# Enable_Pulse_fire.net
KiCad netlist of a schematic drawn in Altium Designer
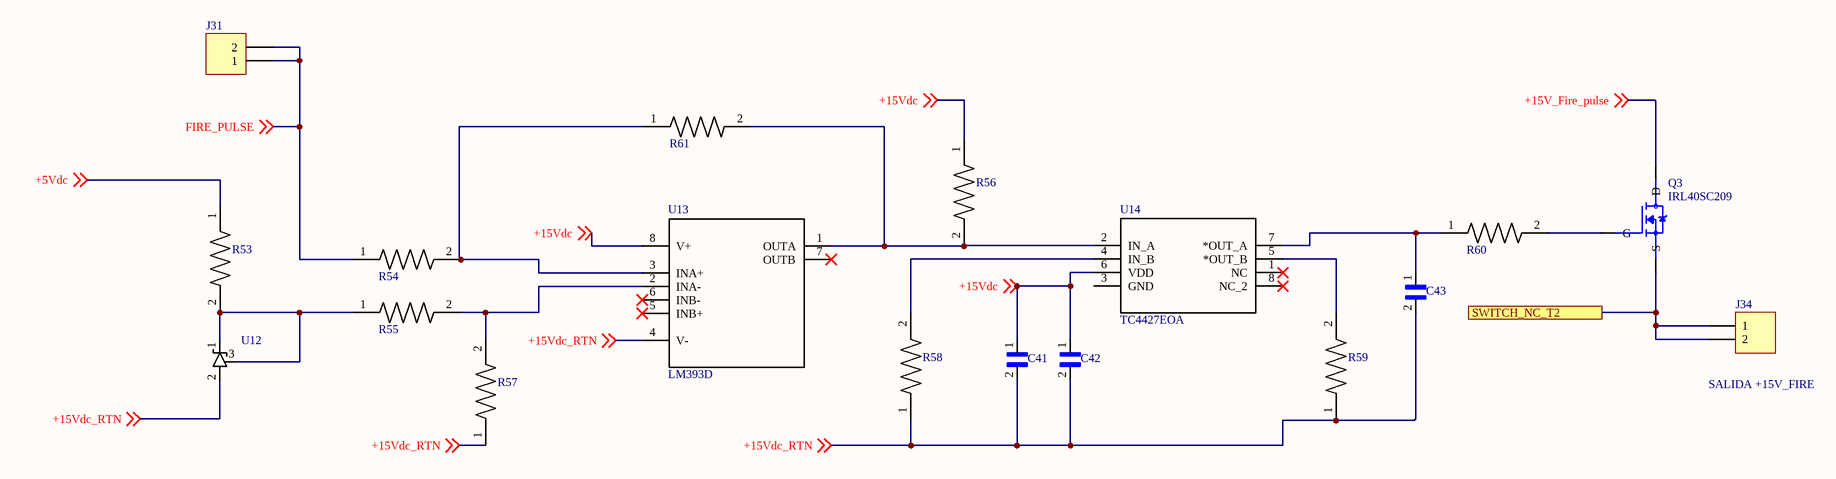
[diagram p0: Enable_Pulse_fire.SchDoc]

(export (version "E")
  (design (tool "Eeschema 10.0.6"))
  (components
    (comp (ref "C41")
      (value "UMK316AC7475KLHTE")
      (footprint "MLCC SMD 1206")
      (description "1216 50V 4.7uF 10% X7S")
      (libsource (lib "Schlib1") (part "Taiyo Yuden"))
    )
    (comp (ref "C42")
      (value "UMF316B7105KLHT")
      (footprint "MLCC SMD 1206")
      (description "1206 50V 1uF 10%")
      (libsource (lib "Schlib1") (part "Taiyo Yuden"))
    )
    (comp (ref "C43")
      (value "UMF316B7103MFHT")
      (footprint "MLCC SMD 1206")
      (description "1206 50V 0.01uF 20%")
      (libsource (lib "Schlib1") (part "Taiyo Yuden"))
    )
    (comp (ref "J31")
      (value "Header 2")
      (footprint "HDR1X2")
      (description "Header, 2-Pin")
      (fields (field (name "PUBLISHER") "Altium Limited"))
      (libsource (lib "Miscellaneous Connectors") (part "Header 2"))
    )
    (comp (ref "J34")
      (value "Header 2")
      (footprint "HDR1X2")
      (description "Header, 2-Pin")
      (fields (field (name "PUBLISHER") "Altium Limited"))
      (libsource (lib "") (part "Header 2_1"))
    )
    (comp (ref "Q3")
      (value "IRL40SC209")
      (footprint "D2PAK-7")
      (description "MOSFET TRENCH <= 40V")
      (libsource (lib "Schlib1") (part "IRL40SC209"))
    )
    (comp (ref "R53")
      (value "RCG12061K00FKEA")
      (footprint "Vishay Resistor 1206")
      (description "1K")
      (libsource (lib "Schlib1") (part "Vishay"))
    )
    (comp (ref "R54")
      (value "RCG12061K00FKEA")
      (footprint "Vishay Resistor 1206")
      (description "1K")
      (libsource (lib "") (part "Vishay_1"))
    )
    (comp (ref "R55")
      (value "RCG12061K00FKEA")
      (footprint "Vishay Resistor 1206")
      (description "1K")
      (libsource (lib "") (part "Vishay_1"))
    )
    (comp (ref "R56")
      (value "RCG12061K00FKEA")
      (footprint "Vishay Resistor 1206")
      (description "1K")
      (libsource (lib "") (part "Vishay_1"))
    )
    (comp (ref "R57")
      (value "CRCW12064K02FKEAC")
      (footprint "Vishay Resistor 1206")
      (description "4K")
      (libsource (lib "") (part "Vishay_1"))
    )
    (comp (ref "R58")
      (value "CRCW12060000Z0EAC")
      (footprint "Vishay Resistor 1206")
      (description "0OHM")
      (libsource (lib "") (part "Vishay_1"))
    )
    (comp (ref "R59")
      (value "CRCW12060000Z0EAC")
      (footprint "Vishay Resistor 1206")
      (description "0OHM")
      (libsource (lib "") (part "Vishay_1"))
    )
    (comp (ref "R60")
      (value "CRCW12064R70FKEAC")
      (footprint "Vishay Resistor 1206")
      (description "4.7OHM")
      (libsource (lib "") (part "Vishay_1"))
    )
    (comp (ref "R61")
      (value "CRCW1206121KFKEA")
      (footprint "Vishay Resistor 1206")
      (description "121K")
      (libsource (lib "") (part "Vishay_1"))
    )
    (comp (ref "U12")
      (value "LM431BIM3/NOPB")
      (footprint "LM431BIM3/NOPB")
      (description "Referencias de voltaje ADJ PREC ZENER SHUNT REG")
      (libsource (lib "Schlib1") (part "LM431BIM3/NOPB"))
    )
    (comp (ref "U13") (value "LM393D") (footprint "SOIC-8") (libsource (lib "Schlib1") (part "LM393D")))
    (comp (ref "U14")
      (value "TC4427EOA")
      (footprint "TC4427EOA")
      (description "Controlador de puerta 1.5A Dual MOSFET Dr NonInver Etemp SOIC8")
      (libsource (lib "Schlib1") (part "TC4427EOA"))
    )
  )
  (nets
    (net (code "1") (name "+5Vdc") (class "Default")
      (node (ref "R53") (pin "1") (pinfunction "1_1") (pintype "passive"))
    )
    (net (code "2") (name "+15V_Fire_pulse") (class "Default")
      (node (ref "Q3") (pin "D") (pinfunction "D_D") (pintype "passive"))
    )
    (net (code "3") (name "+15Vdc") (class "Default")
      (node (ref "C41") (pin "1") (pinfunction "1_1") (pintype "passive"))
      (node (ref "C42") (pin "1") (pinfunction "1_1") (pintype "passive"))
      (node (ref "R56") (pin "1") (pinfunction "1_1") (pintype "passive"))
      (node (ref "U13") (pin "8") (pinfunction "V+_8") (pintype "power_in"))
      (node (ref "U14") (pin "6") (pinfunction "VDD_6") (pintype "power_in"))
    )
    (net (code "4") (name "+15Vdc_RTN") (class "Default")
      (node (ref "C41") (pin "2") (pinfunction "2_2") (pintype "passive"))
      (node (ref "C42") (pin "2") (pinfunction "2_2") (pintype "passive"))
      (node (ref "C43") (pin "2") (pinfunction "2_2") (pintype "passive"))
      (node (ref "R57") (pin "1") (pinfunction "1_1") (pintype "passive"))
      (node (ref "R58") (pin "1") (pinfunction "1_1") (pintype "passive"))
      (node (ref "R59") (pin "1") (pinfunction "1_1") (pintype "passive"))
      (node (ref "U12") (pin "2") (pinfunction "2_2") (pintype "passive"))
      (node (ref "U13") (pin "4") (pinfunction "V-_4") (pintype "power_in"))
    )
    (net (code "5") (name "/SWITCH_NC_T2") (class "Default")
      (node (ref "J34") (pin "1") (pinfunction "1_1") (pintype "passive"))
      (node (ref "J34") (pin "2") (pinfunction "2_2") (pintype "passive"))
      (node (ref "Q3") (pin "S") (pinfunction "S_S") (pintype "passive"))
    )
    (net (code "6") (name "FIRE_PULSE") (class "Default")
      (node (ref "J31") (pin "1") (pinfunction "1_1") (pintype "passive"))
      (node (ref "J31") (pin "2") (pinfunction "2_2") (pintype "passive"))
      (node (ref "R54") (pin "1") (pinfunction "1_1") (pintype "passive"))
    )
    (net (code "7") (name "Net-(Q3-PadG)") (class "Default")
      (node (ref "Q3") (pin "G") (pinfunction "G_G") (pintype "passive"))
      (node (ref "R60") (pin "2") (pinfunction "2_2") (pintype "passive"))
    )
    (net (code "8") (name "Net-(R53-Pad2)") (class "Default")
      (node (ref "R53") (pin "2") (pinfunction "2_2") (pintype "passive"))
      (node (ref "R55") (pin "1") (pinfunction "1_1") (pintype "passive"))
      (node (ref "U12") (pin "1") (pinfunction "1_1") (pintype "passive"))
      (node (ref "U12") (pin "3") (pinfunction "3_3") (pintype "passive"))
    )
    (net (code "9") (name "Net-(U13-INA+)") (class "Default")
      (node (ref "R54") (pin "2") (pinfunction "2_2") (pintype "passive"))
      (node (ref "R61") (pin "1") (pinfunction "1_1") (pintype "passive"))
      (node (ref "U13") (pin "3") (pinfunction "INA+_3") (pintype "passive"))
    )
    (net (code "10") (name "Net-(U13-INA-)") (class "Default")
      (node (ref "R55") (pin "2") (pinfunction "2_2") (pintype "passive"))
      (node (ref "R57") (pin "2") (pinfunction "2_2") (pintype "passive"))
      (node (ref "U13") (pin "2") (pinfunction "INA-_2") (pintype "passive"))
    )
    (net (code "11") (name "Net-(U13-OUTA)") (class "Default")
      (node (ref "R56") (pin "2") (pinfunction "2_2") (pintype "passive"))
      (node (ref "R61") (pin "2") (pinfunction "2_2") (pintype "passive"))
      (node (ref "U13") (pin "1") (pinfunction "OUTA_1") (pintype "passive"))
      (node (ref "U14") (pin "2") (pinfunction "IN_A_2") (pintype "passive"))
    )
    (net (code "12") (name "Net-(U14-*OUT_A)") (class "Default")
      (node (ref "C43") (pin "1") (pinfunction "1_1") (pintype "passive"))
      (node (ref "R60") (pin "1") (pinfunction "1_1") (pintype "passive"))
      (node (ref "U14") (pin "7") (pinfunction "*OUT_A_7") (pintype "passive"))
    )
    (net (code "13") (name "Net-(U14-*OUT_B)") (class "Default")
      (node (ref "R59") (pin "2") (pinfunction "2_2") (pintype "passive"))
      (node (ref "U14") (pin "5") (pinfunction "*OUT_B_5") (pintype "passive"))
    )
    (net (code "14") (name "Net-(U14-IN_B)") (class "Default")
      (node (ref "R58") (pin "2") (pinfunction "2_2") (pintype "passive"))
      (node (ref "U14") (pin "4") (pinfunction "IN_B_4") (pintype "passive"))
    )
    (net (code "15") (name "unconnected-(U13-INB+-Pad5)") (class "Default")
      (node (ref "U13") (pin "5") (pinfunction "INB+_5") (pintype "passive+no_connect"))
    )
    (net (code "16") (name "unconnected-(U13-INB--Pad6)") (class "Default")
      (node (ref "U13") (pin "6") (pinfunction "INB-_6") (pintype "passive+no_connect"))
    )
    (net (code "17") (name "unconnected-(U13-OUTB-Pad7)") (class "Default")
      (node (ref "U13") (pin "7") (pinfunction "OUTB_7") (pintype "passive+no_connect"))
    )
    (net (code "18") (name "unconnected-(U14-GND-Pad3)") (class "Default")
      (node (ref "U14") (pin "3") (pinfunction "GND_3") (pintype "passive"))
    )
    (net (code "19") (name "unconnected-(U14-NC-Pad1)") (class "Default")
      (node (ref "U14") (pin "1") (pinfunction "NC_1") (pintype "passive+no_connect"))
    )
    (net (code "20") (name "unconnected-(U14-NC_2-Pad8)") (class "Default")
      (node (ref "U14") (pin "8") (pinfunction "NC_2_8") (pintype "passive+no_connect"))
    )
  )
)
